# FMBTECH.net
KiCad netlist of a schematic drawn in EAGLE
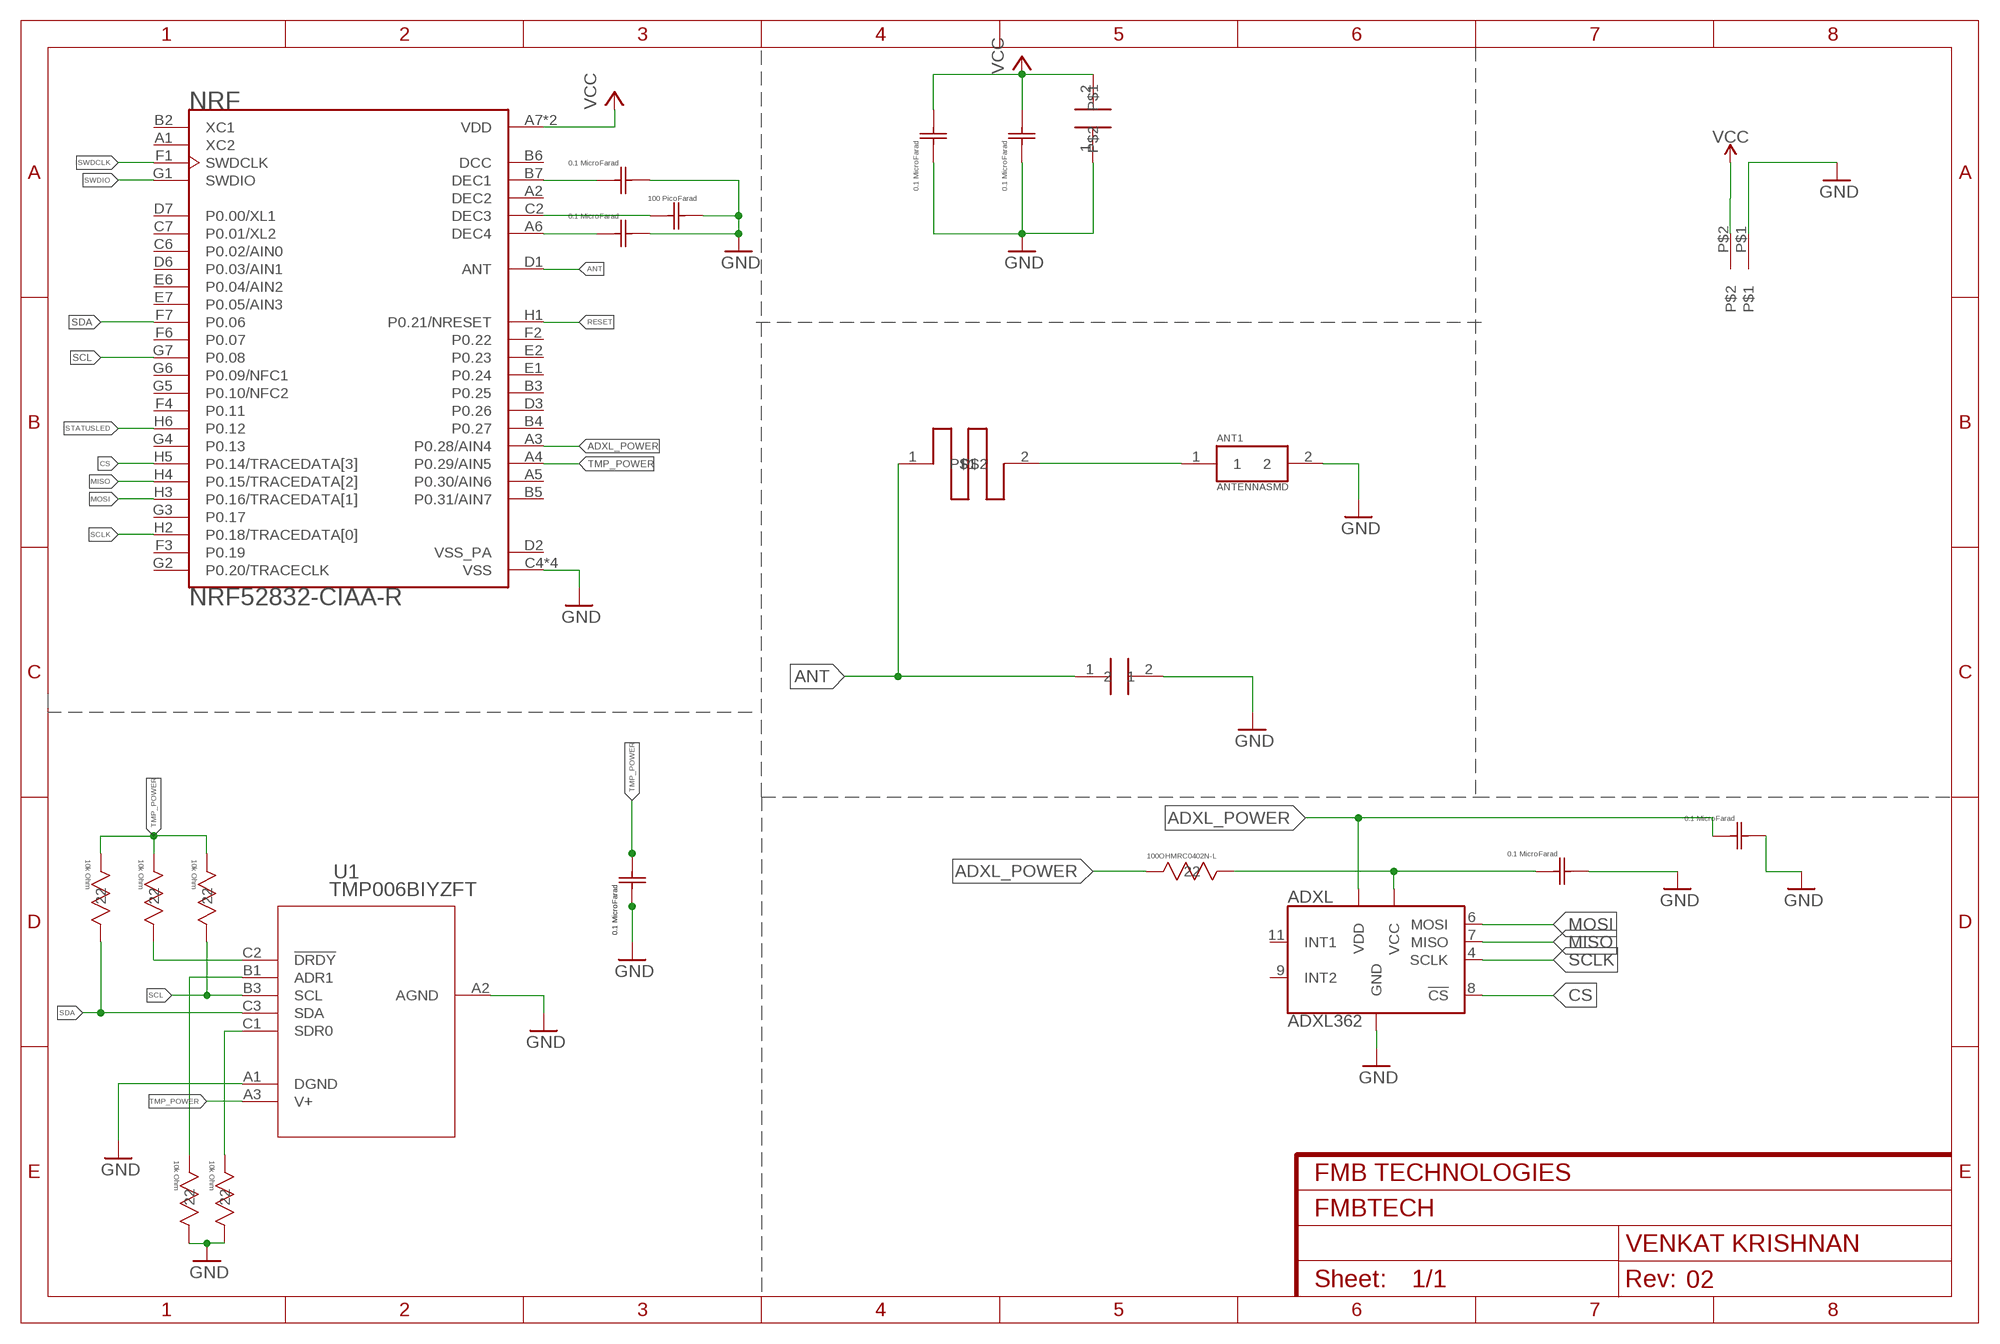
[diagram p0: schematic, sheet 1]

(export (version "E")
  (design (tool "Eeschema 10.0.6"))
  (components
    (comp (ref "ADXL")
      (value "ADXL362")
      (footprint "eagle-import:TFLGA-16_3.3MMX3.1MM")
      (fields (field (name "MF") "Analog Devices") (field (name "MP") "ADXL362BCCZ-RL7"))
      (libsource (lib "eagle-import") (part "ADXL362"))
    )
    (comp (ref "ANT1")
      (value "ANTENNASMD")
      (footprint "eagle-import:1")
      (fields (field (name "MF") "Pulse") (field (name "MP") "W3008"))
      (libsource (lib "eagle-import") (part "ANTENNASMD"))
    )
    (comp (ref "C1")
      (value "02016D104KAT2A")
      (footprint "eagle-import:0201")
      (libsource (lib "eagle-import") (part "02016D104KAT2A"))
    )
    (comp (ref "C2")
      (value "02016D104KAT2A")
      (footprint "eagle-import:0201")
      (libsource (lib "eagle-import") (part "02016D104KAT2A"))
    )
    (comp (ref "C3")
      (value "GRM0335C1E101JA01D")
      (footprint "eagle-import:G-033")
      (libsource (lib "eagle-import") (part "GRM0335C1E101JA01D"))
    )
    (comp (ref "C4")
      (value "02016D104KAT2A")
      (footprint "eagle-import:0201")
      (libsource (lib "eagle-import") (part "02016D104KAT2A"))
    )
    (comp (ref "C5")
      (value "02016D104KAT2A")
      (footprint "eagle-import:0201")
      (libsource (lib "eagle-import") (part "02016D104KAT2A"))
    )
    (comp (ref "C6")
      (value "02016D104KAT2A")
      (footprint "eagle-import:0201")
      (libsource (lib "eagle-import") (part "02016D104KAT2A"))
    )
    (comp (ref "C7")
      (value "02016D104KAT2A")
      (footprint "eagle-import:0201")
      (libsource (lib "eagle-import") (part "02016D104KAT2A"))
    )
    (comp (ref "C8")
      (value "02016D104KAT2A")
      (footprint "eagle-import:0201")
      (libsource (lib "eagle-import") (part "02016D104KAT2A"))
    )
    (comp (ref "C9")
      (value "02016D104KAT2A")
      (footprint "eagle-import:0201")
      (libsource (lib "eagle-import") (part "02016D104KAT2A"))
    )
    (comp (ref "NRF")
      (value "NRF52832-CIAA-R")
      (footprint "eagle-import:BGA50N40P7X8_300X320X40")
      (fields (field (name "MF") "Nordic Semiconductor"))
      (libsource (lib "eagle-import") (part "NRF52832-CIAA-R"))
    )
    (comp (ref "R1")
      (value "RC0402JR-0710KL")
      (footprint "eagle-import:RC0402N")
      (fields (field (name "MANUFACTURER_PART_NUMBER") "RC0402JR0710KL"))
      (libsource (lib "eagle-import") (part "RC0402JR-0710KL"))
    )
    (comp (ref "R2")
      (value "RC0402JR-0710KL")
      (footprint "eagle-import:RC0402N")
      (fields (field (name "MANUFACTURER_PART_NUMBER") "RC0402JR0710KL"))
      (libsource (lib "eagle-import") (part "RC0402JR-0710KL"))
    )
    (comp (ref "R3")
      (value "RC0402JR-0710KL")
      (footprint "eagle-import:RC0402N")
      (fields (field (name "MANUFACTURER_PART_NUMBER") "RC0402JR0710KL"))
      (libsource (lib "eagle-import") (part "RC0402JR-0710KL"))
    )
    (comp (ref "R4")
      (value "RC0402JR-0710KL")
      (footprint "eagle-import:RC0402N")
      (fields (field (name "MANUFACTURER_PART_NUMBER") "RC0402JR0710KL"))
      (libsource (lib "eagle-import") (part "RC0402JR-0710KL"))
    )
    (comp (ref "R5")
      (value "RC0402JR-0710KL")
      (footprint "eagle-import:RC0402N")
      (fields (field (name "MANUFACTURER_PART_NUMBER") "RC0402JR0710KL"))
      (libsource (lib "eagle-import") (part "RC0402JR-0710KL"))
    )
    (comp (ref "R6")
      (value "100OHMRC0402N-L")
      (footprint "eagle-import:RES")
      (fields (field (name "MANUFACTURER_PART_NUMBER") "RC0402FR07100RL"))
      (libsource (lib "eagle-import") (part "100OHMRC0402N-L"))
    )
    (comp (ref "U$1")
      (value "4.7µF")
      (footprint "eagle-import:CAP")
      (libsource (lib "eagle-import") (part "4.7µF"))
    )
    (comp (ref "U$2")
      (value "0.8PF")
      (footprint "eagle-import:CAP")
      (libsource (lib "eagle-import") (part "0.8PF"))
    )
    (comp (ref "U$3")
      (value "INDUCTOR")
      (footprint "eagle-import:1")
      (libsource (lib "eagle-import") (part "INDUCTOR"))
    )
    (comp (ref "U$4")
      (value "SUPPLY")
      (footprint "eagle-import:SUPPLY")
      (libsource (lib "eagle-import") (part "SUPPLY"))
    )
    (comp (ref "U1")
      (value "TMP006BIYZFT")
      (footprint "eagle-import:YZF8")
      (libsource (lib "eagle-import") (part "TMP006BIYZFT"))
    )
  )
  (nets
    (net (code "1") (name "/DCC") (class "Default")
      (node (ref "NRF") (pin "B6") (pinfunction "DCC_B6") (pintype "power_in"))
    )
    (net (code "2") (name "/DEC2") (class "Default")
      (node (ref "NRF") (pin "A2") (pinfunction "DEC2_A2") (pintype "power_in"))
    )
    (net (code "3") (name "/VSS_PA") (class "Default")
      (node (ref "NRF") (pin "D2") (pinfunction "VSS_PA_D2") (pintype "power_in"))
    )
    (net (code "4") (name "ADXL_POWER") (class "Default")
      (node (ref "ADXL") (pin "1") (pinfunction "VDD_1") (pintype "bidirectional"))
      (node (ref "C9") (pin "1") (pinfunction "1_1") (pintype "passive"))
      (node (ref "NRF") (pin "A3") (pinfunction "P0.28/AIN4_A3") (pintype "bidirectional"))
      (node (ref "R6") (pin "1") (pinfunction "11_1") (pintype "passive"))
    )
    (net (code "5") (name "ANT") (class "Default")
      (node (ref "NRF") (pin "D1") (pinfunction "ANT_D1") (pintype "passive"))
      (node (ref "U$2") (pin "1") (pinfunction "1_1") (pintype "bidirectional"))
      (node (ref "U$3") (pin "1") (pinfunction "P$1_1") (pintype "bidirectional"))
    )
    (net (code "6") (name "CS") (class "Default")
      (node (ref "ADXL") (pin "8") (pinfunction "~{CS}_8") (pintype "bidirectional"))
      (node (ref "NRF") (pin "H5") (pinfunction "P0.14/TRACEDATA[3]_H5") (pintype "bidirectional"))
    )
    (net (code "7") (name "GND") (class "Default")
      (node (ref "ADXL") (pin "12") (pinfunction "GND_12") (pintype "bidirectional"))
      (node (ref "ADXL") (pin "13") (pinfunction "GND_13") (pintype "bidirectional"))
      (node (ref "ADXL") (pin "16") (pinfunction "GND_16") (pintype "bidirectional"))
      (node (ref "ANT1") (pin "2") (pinfunction "2_2") (pintype "passive"))
      (node (ref "C1") (pin "2") (pinfunction "2_2") (pintype "passive"))
      (node (ref "C2") (pin "2") (pinfunction "2_2") (pintype "passive"))
      (node (ref "C3") (pin "2") (pinfunction "22_2") (pintype "passive"))
      (node (ref "C4") (pin "1") (pinfunction "1_1") (pintype "passive"))
      (node (ref "C5") (pin "1") (pinfunction "1_1") (pintype "passive"))
      (node (ref "C6") (pin "1") (pinfunction "1_1") (pintype "passive"))
      (node (ref "C7") (pin "1") (pinfunction "1_1") (pintype "passive"))
      (node (ref "C8") (pin "2") (pinfunction "2_2") (pintype "passive"))
      (node (ref "C9") (pin "2") (pinfunction "2_2") (pintype "passive"))
      (node (ref "NRF") (pin "C4") (pinfunction "VSS_C4") (pintype "power_in"))
      (node (ref "NRF") (pin "C5") (pinfunction "VSS_C5") (pintype "power_in"))
      (node (ref "NRF") (pin "E3") (pinfunction "VSS_E3") (pintype "power_in"))
      (node (ref "NRF") (pin "F5") (pinfunction "VSS_F5") (pintype "power_in"))
      (node (ref "R4") (pin "1") (pinfunction "11_1") (pintype "passive"))
      (node (ref "R5") (pin "1") (pinfunction "11_1") (pintype "passive"))
      (node (ref "U$1") (pin "1") (pinfunction "P$1_1") (pintype "bidirectional"))
      (node (ref "U$2") (pin "2") (pinfunction "2_2") (pintype "bidirectional"))
      (node (ref "U$4") (pin "P$1") (pinfunction "P$1_P$1") (pintype "bidirectional"))
      (node (ref "U1") (pin "A1") (pinfunction "DGND_A1") (pintype "power_in"))
      (node (ref "U1") (pin "A2") (pinfunction "AGND_A2") (pintype "power_in"))
    )
    (net (code "8") (name "MISO") (class "Default")
      (node (ref "ADXL") (pin "7") (pinfunction "MISO_7") (pintype "bidirectional"))
      (node (ref "NRF") (pin "H4") (pinfunction "P0.15/TRACEDATA[2]_H4") (pintype "bidirectional"))
    )
    (net (code "9") (name "MOSI") (class "Default")
      (node (ref "ADXL") (pin "6") (pinfunction "MOSI_6") (pintype "bidirectional"))
      (node (ref "NRF") (pin "H3") (pinfunction "P0.16/TRACEDATA[1]_H3") (pintype "bidirectional"))
    )
    (net (code "10") (name "Net-(ADXL-VCC)") (class "Default")
      (node (ref "ADXL") (pin "14") (pinfunction "VCC_14") (pintype "bidirectional"))
      (node (ref "C8") (pin "1") (pinfunction "1_1") (pintype "passive"))
      (node (ref "R6") (pin "2") (pinfunction "22_2") (pintype "passive"))
    )
    (net (code "11") (name "Net-(C3-11)") (class "Default")
      (node (ref "C3") (pin "1") (pinfunction "11_1") (pintype "passive"))
      (node (ref "NRF") (pin "C2") (pinfunction "DEC3_C2") (pintype "power_in"))
    )
    (net (code "12") (name "Net-(NRF-DEC1)") (class "Default")
      (node (ref "C1") (pin "1") (pinfunction "1_1") (pintype "passive"))
      (node (ref "NRF") (pin "B7") (pinfunction "DEC1_B7") (pintype "power_in"))
    )
    (net (code "13") (name "Net-(NRF-DEC4)") (class "Default")
      (node (ref "C2") (pin "1") (pinfunction "1_1") (pintype "passive"))
      (node (ref "NRF") (pin "A6") (pinfunction "DEC4_A6") (pintype "power_in"))
    )
    (net (code "14") (name "Net-(R3-11)") (class "Default")
      (node (ref "R3") (pin "1") (pinfunction "11_1") (pintype "passive"))
      (node (ref "U1") (pin "C2") (pinfunction "~{DRDY}_C2") (pintype "passive"))
    )
    (net (code "15") (name "Net-(R4-22)") (class "Default")
      (node (ref "R4") (pin "2") (pinfunction "22_2") (pintype "passive"))
      (node (ref "U1") (pin "B1") (pinfunction "ADR1_B1") (pintype "passive"))
    )
    (net (code "16") (name "Net-(R5-22)") (class "Default")
      (node (ref "R5") (pin "2") (pinfunction "22_2") (pintype "passive"))
      (node (ref "U1") (pin "C1") (pinfunction "SDR0_C1") (pintype "passive"))
    )
    (net (code "17") (name "Net-(U$3-P$2)") (class "Default")
      (node (ref "ANT1") (pin "1") (pinfunction "1_1") (pintype "passive"))
      (node (ref "U$3") (pin "2") (pinfunction "P$2_2") (pintype "bidirectional"))
    )
    (net (code "18") (name "RESET") (class "Default")
      (node (ref "NRF") (pin "H1") (pinfunction "P0.21/NRESET_H1") (pintype "bidirectional"))
    )
    (net (code "19") (name "SCL") (class "Default")
      (node (ref "NRF") (pin "G7") (pinfunction "P0.08_G7") (pintype "bidirectional"))
      (node (ref "R2") (pin "1") (pinfunction "11_1") (pintype "passive"))
      (node (ref "U1") (pin "B3") (pinfunction "SCL_B3") (pintype "passive"))
    )
    (net (code "20") (name "SCLK") (class "Default")
      (node (ref "ADXL") (pin "4") (pinfunction "SCLK_4") (pintype "bidirectional"))
      (node (ref "NRF") (pin "H2") (pinfunction "P0.18/TRACEDATA[0]_H2") (pintype "bidirectional"))
    )
    (net (code "21") (name "SDA") (class "Default")
      (node (ref "NRF") (pin "F7") (pinfunction "P0.06_F7") (pintype "bidirectional"))
      (node (ref "R1") (pin "1") (pinfunction "11_1") (pintype "passive"))
      (node (ref "U1") (pin "C3") (pinfunction "SDA_C3") (pintype "passive"))
    )
    (net (code "22") (name "STATUSLED") (class "Default")
      (node (ref "NRF") (pin "H6") (pinfunction "P0.12_H6") (pintype "bidirectional"))
    )
    (net (code "23") (name "SWDCLK") (class "Default")
      (node (ref "NRF") (pin "F1") (pinfunction "SWDCLK_F1") (pintype "input"))
    )
    (net (code "24") (name "SWDIO") (class "Default")
      (node (ref "NRF") (pin "G1") (pinfunction "SWDIO_G1") (pintype "bidirectional"))
    )
    (net (code "25") (name "TMP_POWER") (class "Default")
      (node (ref "C4") (pin "2") (pinfunction "2_2") (pintype "passive"))
      (node (ref "C5") (pin "2") (pinfunction "2_2") (pintype "passive"))
      (node (ref "NRF") (pin "A4") (pinfunction "P0.29/AIN5_A4") (pintype "bidirectional"))
      (node (ref "R1") (pin "2") (pinfunction "22_2") (pintype "passive"))
      (node (ref "R2") (pin "2") (pinfunction "22_2") (pintype "passive"))
      (node (ref "R3") (pin "2") (pinfunction "22_2") (pintype "passive"))
      (node (ref "U1") (pin "A3") (pinfunction "V+_A3") (pintype "power_in"))
    )
    (net (code "26") (name "VCC") (class "Default")
      (node (ref "C6") (pin "2") (pinfunction "2_2") (pintype "passive"))
      (node (ref "C7") (pin "2") (pinfunction "2_2") (pintype "passive"))
      (node (ref "NRF") (pin "A7") (pinfunction "VDD_A7") (pintype "power_in"))
      (node (ref "NRF") (pin "H7") (pinfunction "VDD_H7") (pintype "power_in"))
      (node (ref "U$1") (pin "2") (pinfunction "P$2_2") (pintype "bidirectional"))
      (node (ref "U$4") (pin "P$2") (pinfunction "P$2_P$2") (pintype "bidirectional"))
    )
    (net (code "27") (name "unconnected-(ADXL-INT1-Pad11)") (class "Default")
      (node (ref "ADXL") (pin "11") (pinfunction "INT1_11") (pintype "bidirectional"))
    )
    (net (code "28") (name "unconnected-(ADXL-INT2-Pad9)") (class "Default")
      (node (ref "ADXL") (pin "9") (pinfunction "INT2_9") (pintype "bidirectional"))
    )
    (net (code "29") (name "unconnected-(NRF-P0.00{slash}XL1-PadD7)") (class "Default")
      (node (ref "NRF") (pin "D7") (pinfunction "P0.00/XL1_D7") (pintype "bidirectional"))
    )
    (net (code "30") (name "unconnected-(NRF-P0.01{slash}XL2-PadC7)") (class "Default")
      (node (ref "NRF") (pin "C7") (pinfunction "P0.01/XL2_C7") (pintype "bidirectional"))
    )
    (net (code "31") (name "unconnected-(NRF-P0.02{slash}AIN0-PadC6)") (class "Default")
      (node (ref "NRF") (pin "C6") (pinfunction "P0.02/AIN0_C6") (pintype "bidirectional"))
    )
    (net (code "32") (name "unconnected-(NRF-P0.03{slash}AIN1-PadD6)") (class "Default")
      (node (ref "NRF") (pin "D6") (pinfunction "P0.03/AIN1_D6") (pintype "bidirectional"))
    )
    (net (code "33") (name "unconnected-(NRF-P0.04{slash}AIN2-PadE6)") (class "Default")
      (node (ref "NRF") (pin "E6") (pinfunction "P0.04/AIN2_E6") (pintype "bidirectional"))
    )
    (net (code "34") (name "unconnected-(NRF-P0.05{slash}AIN3-PadE7)") (class "Default")
      (node (ref "NRF") (pin "E7") (pinfunction "P0.05/AIN3_E7") (pintype "bidirectional"))
    )
    (net (code "35") (name "unconnected-(NRF-P0.07-PadF6)") (class "Default")
      (node (ref "NRF") (pin "F6") (pinfunction "P0.07_F6") (pintype "bidirectional"))
    )
    (net (code "36") (name "unconnected-(NRF-P0.09{slash}NFC1-PadG6)") (class "Default")
      (node (ref "NRF") (pin "G6") (pinfunction "P0.09/NFC1_G6") (pintype "bidirectional"))
    )
    (net (code "37") (name "unconnected-(NRF-P0.10{slash}NFC2-PadG5)") (class "Default")
      (node (ref "NRF") (pin "G5") (pinfunction "P0.10/NFC2_G5") (pintype "bidirectional"))
    )
    (net (code "38") (name "unconnected-(NRF-P0.11-PadF4)") (class "Default")
      (node (ref "NRF") (pin "F4") (pinfunction "P0.11_F4") (pintype "bidirectional"))
    )
    (net (code "39") (name "unconnected-(NRF-P0.13-PadG4)") (class "Default")
      (node (ref "NRF") (pin "G4") (pinfunction "P0.13_G4") (pintype "bidirectional"))
    )
    (net (code "40") (name "unconnected-(NRF-P0.17-PadG3)") (class "Default")
      (node (ref "NRF") (pin "G3") (pinfunction "P0.17_G3") (pintype "bidirectional"))
    )
    (net (code "41") (name "unconnected-(NRF-P0.19-PadF3)") (class "Default")
      (node (ref "NRF") (pin "F3") (pinfunction "P0.19_F3") (pintype "bidirectional"))
    )
    (net (code "42") (name "unconnected-(NRF-P0.20{slash}TRACECLK-PadG2)") (class "Default")
      (node (ref "NRF") (pin "G2") (pinfunction "P0.20/TRACECLK_G2") (pintype "bidirectional"))
    )
    (net (code "43") (name "unconnected-(NRF-P0.22-PadF2)") (class "Default")
      (node (ref "NRF") (pin "F2") (pinfunction "P0.22_F2") (pintype "bidirectional"))
    )
    (net (code "44") (name "unconnected-(NRF-P0.23-PadE2)") (class "Default")
      (node (ref "NRF") (pin "E2") (pinfunction "P0.23_E2") (pintype "bidirectional"))
    )
    (net (code "45") (name "unconnected-(NRF-P0.24-PadE1)") (class "Default")
      (node (ref "NRF") (pin "E1") (pinfunction "P0.24_E1") (pintype "bidirectional"))
    )
    (net (code "46") (name "unconnected-(NRF-P0.25-PadB3)") (class "Default")
      (node (ref "NRF") (pin "B3") (pinfunction "P0.25_B3") (pintype "bidirectional"))
    )
    (net (code "47") (name "unconnected-(NRF-P0.26-PadD3)") (class "Default")
      (node (ref "NRF") (pin "D3") (pinfunction "P0.26_D3") (pintype "bidirectional"))
    )
    (net (code "48") (name "unconnected-(NRF-P0.27-PadB4)") (class "Default")
      (node (ref "NRF") (pin "B4") (pinfunction "P0.27_B4") (pintype "bidirectional"))
    )
    (net (code "49") (name "unconnected-(NRF-P0.30{slash}AIN6-PadA5)") (class "Default")
      (node (ref "NRF") (pin "A5") (pinfunction "P0.30/AIN6_A5") (pintype "bidirectional"))
    )
    (net (code "50") (name "unconnected-(NRF-P0.31{slash}AIN7-PadB5)") (class "Default")
      (node (ref "NRF") (pin "B5") (pinfunction "P0.31/AIN7_B5") (pintype "bidirectional"))
    )
    (net (code "51") (name "unconnected-(NRF-XC1-PadB2)") (class "Default")
      (node (ref "NRF") (pin "B2") (pinfunction "XC1_B2") (pintype "input"))
    )
    (net (code "52") (name "unconnected-(NRF-XC2-PadA1)") (class "Default")
      (node (ref "NRF") (pin "A1") (pinfunction "XC2_A1") (pintype "input"))
    )
  )
)
